# Sheet2_0.net
KiCad netlist of a schematic drawn in Altium Designer
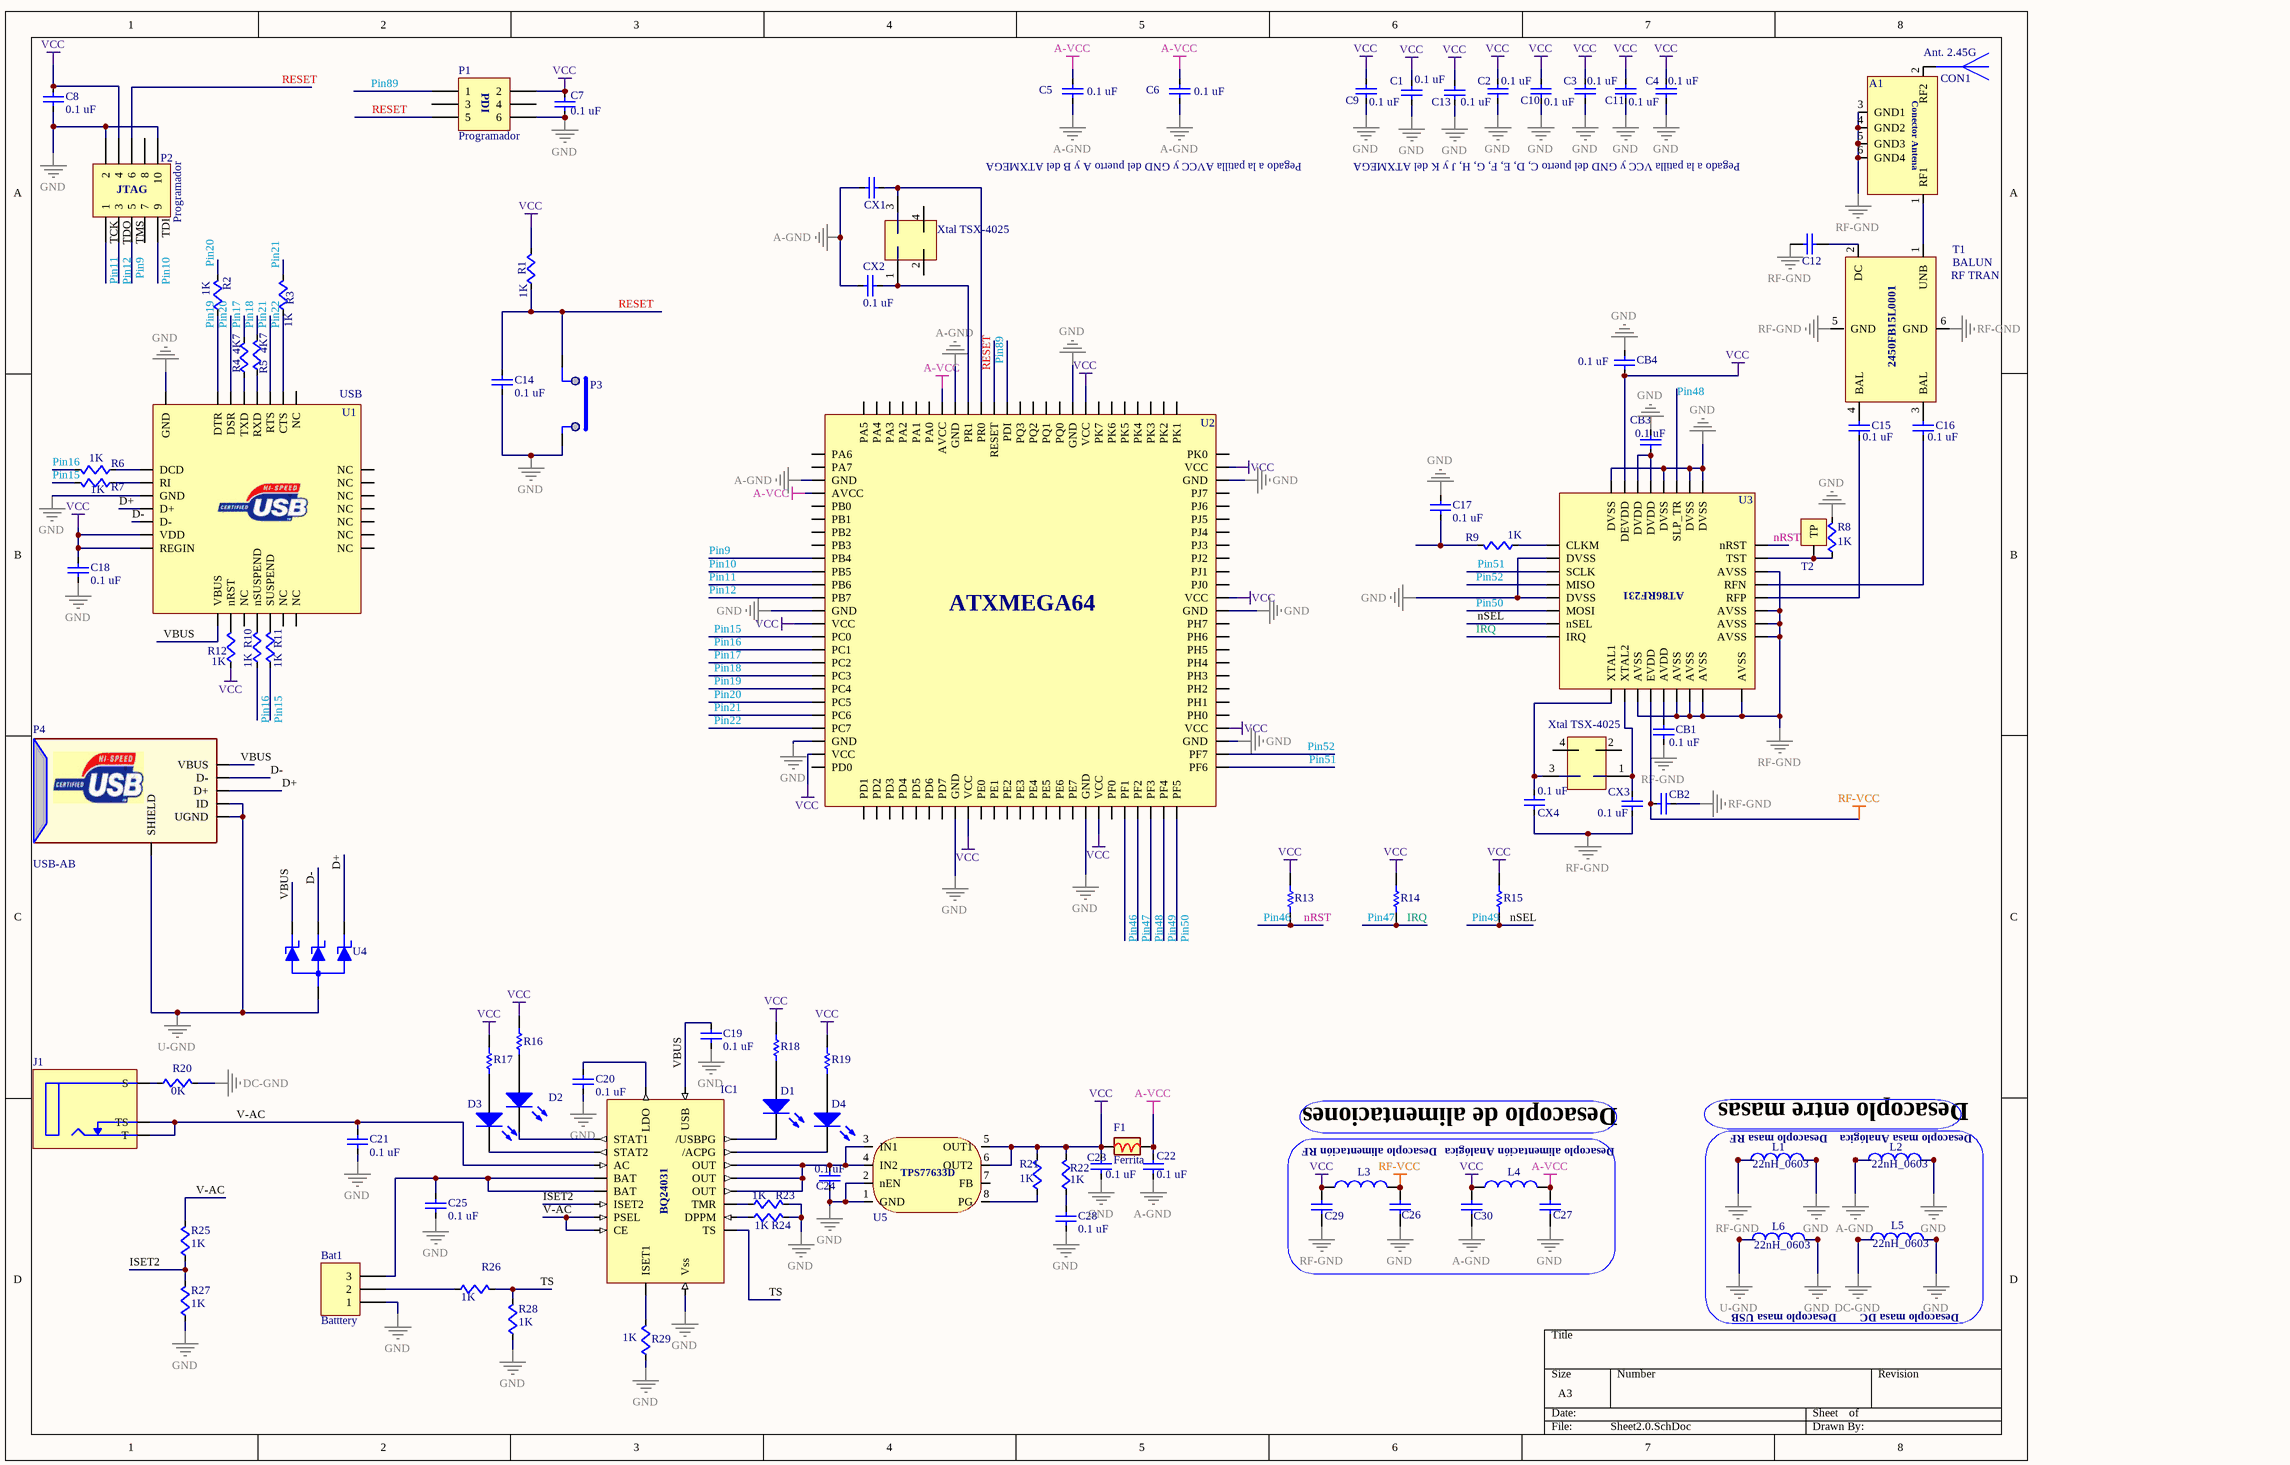
[diagram p0: Sheet2.0.SchDoc]

(export (version "E")
  (design (tool "Eeschema 10.0.6"))
  (components
    (comp (ref "A1")
      (value "Ant. 2.45G")
      (footprint "ANTENNA CHIP")
      (description "ANTENNA CHIP 2.4GHZ")
      (libsource (lib "Mia") (part "2450AT18A100"))
    )
    (comp (ref "Bat1")
      (value "Batttery")
      (footprint "HDR1X3")
      (description "Header, 3-Pin")
      (fields (field (name "PUBLISHER") "Altium Limited"))
      (libsource (lib "Mia") (part "Header 3"))
    )
    (comp (ref "C1")
      (value "C")
      (footprint "0402")
      (description "CONDENSADOR")
      (fields (field (name "VALOR") "0.1 uF"))
      (libsource (lib "Mia") (part "C"))
    )
    (comp (ref "C2")
      (value "C")
      (footprint "0402")
      (description "CONDENSADOR")
      (fields (field (name "VALOR") "0.1 uF"))
      (libsource (lib "Mia") (part "C"))
    )
    (comp (ref "C3")
      (value "C")
      (footprint "0402")
      (description "CONDENSADOR")
      (fields (field (name "VALOR") "0.1 uF"))
      (libsource (lib "Mia") (part "C"))
    )
    (comp (ref "C4")
      (value "C")
      (footprint "0402")
      (description "CONDENSADOR")
      (fields (field (name "VALOR") "0.1 uF"))
      (libsource (lib "Mia") (part "C"))
    )
    (comp (ref "C5")
      (value "C")
      (footprint "0402")
      (description "CONDENSADOR")
      (fields (field (name "VALOR") "0.1 uF"))
      (libsource (lib "Mia") (part "C"))
    )
    (comp (ref "C6")
      (value "C")
      (footprint "0402")
      (description "CONDENSADOR")
      (fields (field (name "VALOR") "0.1 uF"))
      (libsource (lib "Mia") (part "C"))
    )
    (comp (ref "C7")
      (value "C")
      (footprint "0402")
      (description "CONDENSADOR")
      (fields (field (name "VALOR") "0.1 uF"))
      (libsource (lib "Mia") (part "C"))
    )
    (comp (ref "C8")
      (value "C")
      (footprint "0402")
      (description "CONDENSADOR")
      (fields (field (name "VALOR") "0.1 uF"))
      (libsource (lib "Mia") (part "C"))
    )
    (comp (ref "C9")
      (value "C")
      (footprint "0402")
      (description "CONDENSADOR")
      (fields (field (name "VALOR") "0.1 uF"))
      (libsource (lib "Mia") (part "C"))
    )
    (comp (ref "C10")
      (value "C")
      (footprint "0402")
      (description "CONDENSADOR")
      (fields (field (name "VALOR") "0.1 uF"))
      (libsource (lib "Mia") (part "C"))
    )
    (comp (ref "C11")
      (value "C")
      (footprint "0402")
      (description "CONDENSADOR")
      (fields (field (name "VALOR") "0.1 uF"))
      (libsource (lib "Mia") (part "C"))
    )
    (comp (ref "C12")
      (value "22pF_0402")
      (footprint "0402")
      (description "CAP CER 56PF 50V 5% C0G 0402")
      (libsource (lib "Mia") (part "56pF_0402"))
    )
    (comp (ref "C13")
      (value "C")
      (footprint "0402")
      (description "CONDENSADOR")
      (fields (field (name "VALOR") "0.1 uF"))
      (libsource (lib "Mia") (part "C"))
    )
    (comp (ref "C14")
      (value "C")
      (footprint "0402")
      (description "CONDENSADOR")
      (fields (field (name "VALOR") "0.1 uF"))
      (libsource (lib "Mia") (part "C"))
    )
    (comp (ref "C15")
      (value "C")
      (footprint "0402")
      (description "CONDENSADOR")
      (fields (field (name "VALOR") "0.1 uF"))
      (libsource (lib "Mia") (part "C"))
    )
    (comp (ref "C16")
      (value "C")
      (footprint "0402")
      (description "CONDENSADOR")
      (fields (field (name "VALOR") "0.1 uF"))
      (libsource (lib "Mia") (part "C"))
    )
    (comp (ref "C17")
      (value "C")
      (footprint "0402")
      (description "CONDENSADOR")
      (fields (field (name "VALOR") "0.1 uF"))
      (libsource (lib "Mia") (part "C"))
    )
    (comp (ref "C18")
      (value "C")
      (footprint "0402")
      (description "CONDENSADOR")
      (fields (field (name "VALOR") "0.1 uF"))
      (libsource (lib "Mia") (part "C"))
    )
    (comp (ref "C19")
      (value "C")
      (footprint "0402")
      (description "CONDENSADOR")
      (fields (field (name "VALOR") "0.1 uF"))
      (libsource (lib "Mia") (part "C"))
    )
    (comp (ref "C20")
      (value "C")
      (footprint "0402")
      (description "CONDENSADOR")
      (fields (field (name "VALOR") "0.1 uF"))
      (libsource (lib "Mia") (part "C"))
    )
    (comp (ref "C21")
      (value "C")
      (footprint "0402")
      (description "CONDENSADOR")
      (fields (field (name "VALOR") "0.1 uF"))
      (libsource (lib "Mia") (part "C"))
    )
    (comp (ref "C22")
      (value "C")
      (footprint "0402")
      (description "CONDENSADOR")
      (fields (field (name "VALOR") "0.1 uF"))
      (libsource (lib "Mia") (part "C"))
    )
    (comp (ref "C23")
      (value "C")
      (footprint "0402")
      (description "CONDENSADOR")
      (fields (field (name "VALOR") "0.1 uF"))
      (libsource (lib "Mia") (part "C"))
    )
    (comp (ref "C24")
      (value "C")
      (footprint "0402")
      (description "CONDENSADOR")
      (fields (field (name "VALOR") "0.1 uF"))
      (libsource (lib "Mia") (part "C"))
    )
    (comp (ref "C25")
      (value "C")
      (footprint "0402")
      (description "CONDENSADOR")
      (fields (field (name "VALOR") "0.1 uF"))
      (libsource (lib "Mia") (part "C"))
    )
    (comp (ref "C26")
      (value "100nF_0805")
      (footprint "0805")
      (description "CAP CER 100PF 630V X7R 0805")
      (libsource (lib "Mia") (part "100nF_0805"))
    )
    (comp (ref "C27")
      (value "100nF_0805")
      (footprint "0805")
      (description "CAP CER 100PF 630V X7R 0805")
      (libsource (lib "Mia") (part "100nF_0805"))
    )
    (comp (ref "C28")
      (value "C")
      (footprint "0402")
      (description "CONDENSADOR")
      (fields (field (name "VALOR") "0.1 uF"))
      (libsource (lib "Mia") (part "C"))
    )
    (comp (ref "C29")
      (value "100nF_0805")
      (footprint "0805")
      (description "CAP CER 100PF 630V X7R 0805")
      (libsource (lib "Mia") (part "100nF_0805"))
    )
    (comp (ref "C30")
      (value "100nF_0805")
      (footprint "0805")
      (description "CAP CER 100PF 630V X7R 0805")
      (libsource (lib "Mia") (part "100nF_0805"))
    )
    (comp (ref "CB1")
      (value "C")
      (footprint "0402")
      (description "CONDENSADOR")
      (fields (field (name "VALOR") "0.1 uF"))
      (libsource (lib "Mia") (part "C"))
    )
    (comp (ref "CB2")
      (value "C")
      (footprint "0402")
      (description "CONDENSADOR")
      (fields (field (name "VALOR") "0.1 uF"))
      (libsource (lib "Mia") (part "C"))
    )
    (comp (ref "CB3")
      (value "C")
      (footprint "0402")
      (description "CONDENSADOR")
      (fields (field (name "VALOR") "0.1 uF"))
      (libsource (lib "Mia") (part "C"))
    )
    (comp (ref "CB4")
      (value "C")
      (footprint "0402")
      (description "CONDENSADOR")
      (fields (field (name "VALOR") "0.1 uF"))
      (libsource (lib "Mia") (part "C"))
    )
    (comp (ref "CON1")
      (value "Conector Antena")
      (footprint "MM8430-2600_Coaxial Connectors")
      (description "CONN MW COAXIAL WITH SWITCH")
      (libsource (lib "Mia") (part "CON ANT-MM8430-2600RA1"))
    )
    (comp (ref "CX1")
      (value "C")
      (footprint "0402")
      (description "CONDENSADOR")
      (libsource (lib "Mia") (part "C"))
    )
    (comp (ref "CX2")
      (value "C")
      (footprint "0402")
      (description "CONDENSADOR")
      (fields (field (name "VALOR") "0.1 uF"))
      (libsource (lib "Mia") (part "C"))
    )
    (comp (ref "CX3")
      (value "C")
      (footprint "0402")
      (description "CONDENSADOR")
      (fields (field (name "VALOR") "0.1 uF"))
      (libsource (lib "Mia") (part "C"))
    )
    (comp (ref "CX4")
      (value "C")
      (footprint "0402")
      (description "CONDENSADOR")
      (libsource (lib "Mia") (part "C"))
    )
    (comp (ref "D1")
      (value "Diodo Led")
      (footprint "Diode Led")
      (description "Typical INFRARED GaAs LED")
      (libsource (lib "Mia") (part "LTST-C230CKT"))
    )
    (comp (ref "D2")
      (value "Diodo Led")
      (footprint "Diode Led")
      (description "Typical INFRARED GaAs LED")
      (libsource (lib "Mia") (part "LTST-C230CKT"))
    )
    (comp (ref "D3")
      (value "Diodo Led")
      (footprint "Diode Led")
      (description "Typical INFRARED GaAs LED")
      (libsource (lib "Mia") (part "LTST-C230CKT"))
    )
    (comp (ref "D4")
      (value "Diodo Led")
      (footprint "Diode Led")
      (description "Typical INFRARED GaAs LED")
      (libsource (lib "Mia") (part "LTST-C230CKT"))
    )
    (comp (ref "F1")
      (value "Ferrita")
      (footprint "0603")
      (description "Chip Ferrite Beads")
      (libsource (lib "Mia") (part "BLM21AH102SN1"))
    )
    (comp (ref "IC1")
      (value "BQ24031")
      (footprint "BQ24031")
      (description "IC PWR MANAGEMENT SYSTEM 20-QFN")
      (libsource (lib "Mia") (part "BQ24031"))
    )
    (comp (ref "J1")
      (value "CAMSHOT")
      (footprint "MJ-2509N")
      (description "CONN MONO JACK 2.5MM PCB MNT")
      (libsource (lib "*") (part "MJ-2509N_1"))
    )
    (comp (ref "L1")
      (value "22nH_0603")
      (footprint "0603")
      (description "CER INDUCTOR 22NH 0603")
      (libsource (lib "Mia") (part "22nH_0603"))
    )
    (comp (ref "L2")
      (value "22nH_0603")
      (footprint "0603")
      (description "CER INDUCTOR 22NH 0603")
      (libsource (lib "Mia") (part "22nH_0603"))
    )
    (comp (ref "L3")
      (value "22nH_0603")
      (footprint "0603")
      (description "CER INDUCTOR 22NH 0603")
      (libsource (lib "Mia") (part "22nH_0603"))
    )
    (comp (ref "L4")
      (value "22nH_0603")
      (footprint "0603")
      (description "CER INDUCTOR 22NH 0603")
      (libsource (lib "Mia") (part "22nH_0603"))
    )
    (comp (ref "L5")
      (value "22nH_0603")
      (footprint "0603")
      (description "CER INDUCTOR 22NH 0603")
      (libsource (lib "Mia") (part "22nH_0603"))
    )
    (comp (ref "L6")
      (value "22nH_0603")
      (footprint "0603")
      (description "CER INDUCTOR 22NH 0603")
      (libsource (lib "Mia") (part "22nH_0603"))
    )
    (comp (ref "P1")
      (value "Programador")
      (footprint "HDR2X3")
      (description "Header, 3-Pin, Dual row")
      (fields (field (name "PUBLISHER") "Altium Limited"))
      (libsource (lib "Mia") (part "Header 3X2"))
    )
    (comp (ref "P2")
      (value "Programador")
      (footprint "HDR2X5")
      (description "Header, 5-Pin, Dual row")
      (fields (field (name "PUBLISHER") "Altium Limited"))
      (libsource (lib "Mia") (part "Header 5X2"))
    )
    (comp (ref "P3")
      (value "Pulsador")
      (footprint "PUSH-BUTTON-W")
      (description "SWITCH TACT 6X3.5MM H=4.3MM 180G")
      (libsource (lib "Mia") (part "PUSHBUTTON"))
    )
    (comp (ref "P4")
      (value "USB-AB")
      (footprint "USB-MINI-AB-SMT")
      (description "CONN RECEPT USB 5POS RT ANG SMD")
      (libsource (lib "Mia") (part "WM1722"))
    )
    (comp (ref "R1")
      (value "1K")
      (footprint "0603")
      (description "RESISTENCIA 0402 SMD")
      (fields (field (name "Comment") "R 0402"))
      (libsource (lib "Mia") (part "R 0402"))
    )
    (comp (ref "R2")
      (value "1K")
      (footprint "0603")
      (description "RESISTENCIA 0402 SMD")
      (fields (field (name "Comment") "R 0402"))
      (libsource (lib "Mia") (part "R 0402"))
    )
    (comp (ref "R3")
      (value "1K")
      (footprint "0603")
      (description "RESISTENCIA 0402 SMD")
      (fields (field (name "Comment") "R 0402"))
      (libsource (lib "Mia") (part "R 0402"))
    )
    (comp (ref "R4")
      (value "4K7")
      (footprint "0603")
      (description "RESISTENCIA 0402 SMD")
      (fields (field (name "Comment") "R 0402"))
      (libsource (lib "Mia") (part "R 0402"))
    )
    (comp (ref "R5")
      (value "4K7")
      (footprint "0603")
      (description "RESISTENCIA 0402 SMD")
      (fields (field (name "Comment") "R 0402"))
      (libsource (lib "Mia") (part "R 0402"))
    )
    (comp (ref "R6")
      (value "1K")
      (footprint "0603")
      (description "RESISTENCIA 0402 SMD")
      (fields (field (name "Comment") "R 0402"))
      (libsource (lib "Mia") (part "R 0402"))
    )
    (comp (ref "R7")
      (value "1K")
      (footprint "0603")
      (description "RESISTENCIA 0402 SMD")
      (fields (field (name "Comment") "R 0402"))
      (libsource (lib "Mia") (part "R 0402"))
    )
    (comp (ref "R8")
      (value "1K")
      (footprint "0603")
      (description "RESISTENCIA 0402 SMD")
      (fields (field (name "Comment") "R 0402"))
      (libsource (lib "Mia") (part "R 0402"))
    )
    (comp (ref "R9")
      (value "1K")
      (footprint "0603")
      (description "RESISTENCIA 0402 SMD")
      (fields (field (name "Comment") "R 0402"))
      (libsource (lib "Mia") (part "R 0402"))
    )
    (comp (ref "R10")
      (value "1K")
      (footprint "0603")
      (description "RESISTENCIA 0402 SMD")
      (fields (field (name "Comment") "R 0402"))
      (libsource (lib "Mia") (part "R 0402"))
    )
    (comp (ref "R11")
      (value "1K")
      (footprint "0603")
      (description "RESISTENCIA 0402 SMD")
      (fields (field (name "Comment") "R 0402"))
      (libsource (lib "Mia") (part "R 0402"))
    )
    (comp (ref "R12")
      (value "1K")
      (footprint "0603")
      (description "RESISTENCIA 0402 SMD")
      (fields (field (name "Comment") "R 0402"))
      (libsource (lib "Mia") (part "R 0402"))
    )
    (comp (ref "R13")
      (value "16.9kohm-0805")
      (footprint "0805")
      (description "RES 16.9K OHM 1/8W 1% 0805 SMD")
      (libsource (lib "Mia") (part "16.9kohm-0805"))
    )
    (comp (ref "R14")
      (value "16.9kohm-0805")
      (footprint "0805")
      (description "RES 16.9K OHM 1/8W 1% 0805 SMD")
      (libsource (lib "Mia") (part "16.9kohm-0805"))
    )
    (comp (ref "R15")
      (value "16.9kohm-0805")
      (footprint "0805")
      (description "RES 16.9K OHM 1/8W 1% 0805 SMD")
      (libsource (lib "Mia") (part "16.9kohm-0805"))
    )
    (comp (ref "R16")
      (value "16.9kohm-0805")
      (footprint "0805")
      (description "RES 16.9K OHM 1/8W 1% 0805 SMD")
      (libsource (lib "Mia") (part "16.9kohm-0805"))
    )
    (comp (ref "R17")
      (value "16.9kohm-0805")
      (footprint "0805")
      (description "RES 16.9K OHM 1/8W 1% 0805 SMD")
      (libsource (lib "Mia") (part "16.9kohm-0805"))
    )
    (comp (ref "R18")
      (value "16.9kohm-0805")
      (footprint "0805")
      (description "RES 16.9K OHM 1/8W 1% 0805 SMD")
      (libsource (lib "Mia") (part "16.9kohm-0805"))
    )
    (comp (ref "R19")
      (value "16.9kohm-0805")
      (footprint "0805")
      (description "RES 16.9K OHM 1/8W 1% 0805 SMD")
      (libsource (lib "Mia") (part "16.9kohm-0805"))
    )
    (comp (ref "R20")
      (value "0K")
      (footprint "0603")
      (description "RESISTENCIA 0402 SMD")
      (fields (field (name "Comment") "R 0402"))
      (libsource (lib "Mia") (part "R 0402"))
    )
    (comp (ref "R21")
      (value "1K")
      (footprint "0603")
      (description "RESISTENCIA 0402 SMD")
      (fields (field (name "Comment") "R 0402"))
      (libsource (lib "Mia") (part "R 0402"))
    )
    (comp (ref "R22")
      (value "1K")
      (footprint "0603")
      (description "RESISTENCIA 0402 SMD")
      (fields (field (name "Comment") "R 0402"))
      (libsource (lib "Mia") (part "R 0402"))
    )
    (comp (ref "R23")
      (value "1K")
      (footprint "0603")
      (description "RESISTENCIA 0402 SMD")
      (fields (field (name "Comment") "R 0402"))
      (libsource (lib "Mia") (part "R 0402"))
    )
    (comp (ref "R24")
      (value "1K")
      (footprint "0603")
      (description "RESISTENCIA 0402 SMD")
      (fields (field (name "Comment") "R 0402"))
      (libsource (lib "Mia") (part "R 0402"))
    )
    (comp (ref "R25")
      (value "1K")
      (footprint "0603")
      (description "RESISTENCIA 0402 SMD")
      (fields (field (name "Comment") "R 0402"))
      (libsource (lib "Mia") (part "R 0402"))
    )
    (comp (ref "R26")
      (value "1K")
      (footprint "0603")
      (description "RESISTENCIA 0402 SMD")
      (fields (field (name "Comment") "R 0402"))
      (libsource (lib "Mia") (part "R 0402"))
    )
    (comp (ref "R27")
      (value "1K")
      (footprint "0603")
      (description "RESISTENCIA 0402 SMD")
      (fields (field (name "Comment") "R 0402"))
      (libsource (lib "Mia") (part "R 0402"))
    )
    (comp (ref "R28")
      (value "1K")
      (footprint "0603")
      (description "RESISTENCIA 0402 SMD")
      (fields (field (name "Comment") "R 0402"))
      (libsource (lib "Mia") (part "R 0402"))
    )
    (comp (ref "R29")
      (value "1K")
      (footprint "0603")
      (description "RESISTENCIA 0402 SMD")
      (fields (field (name "Comment") "R 0402"))
      (libsource (lib "Mia") (part "R 0402"))
    )
    (comp (ref "T1")
      (value "BALUN")
      (footprint "BALUN")
      (description "FILTER BALUN CER CHIP 2.4GHZ")
      (libsource (lib "Mia") (part "2450FB39B100E"))
    )
    (comp (ref "T2")
      (value "TESTPOINT")
      (footprint "TESTPOINT")
      (description "Punto de Test")
      (libsource (lib "Mia") (part "TESTPOINT"))
    )
    (comp (ref "U1")
      (value "USB")
      (footprint "QFN28_5X5")
      (description "IC USB-TO-UART BRIDGE 28MLP")
      (libsource (lib "Mia") (part "CP2102"))
    )
    (comp (ref "U2")
      (value "XMEGA")
      (footprint "Quad100")
      (description "MCU AVR 64K FLASH 1.6V 100-TQFP")
      (libsource (lib "Mia") (part "ATXMEGA64A1"))
    )
    (comp (ref "U3")
      (value "RF TRAN")
      (footprint "QFN32_50")
      (description "IC TXRX ZIGBEE/802.15.4 32QFN")
      (libsource (lib "Mia") (part "AT86RF231"))
    )
    (comp (ref "U4")
      (value "TVS")
      (footprint "SOT-143")
      (description "TVS AVAL DIODE ARRAY 3 CH SOT143")
      (libsource (lib "Mia") (part "SP0503BAHTG"))
    )
    (comp (ref "U5")
      (value "TPS77633D")
      (footprint "TPS77633D")
      (description "IC 3.3V 500MA LDO REG 8-SOIC")
      (libsource (lib "Mia") (part "TPS77633D"))
    )
    (comp (ref "Xtal1")
      (value "Xtal TSX-4025")
      (footprint "TSX-4025")
      (description "Cristal 16Mhz")
      (libsource (lib "Mia") (part "Xtal TSX-4025"))
    )
    (comp (ref "Xtal2")
      (value "Xtal TSX-4025")
      (footprint "TSX-4025")
      (description "Cristal 16Mhz")
      (libsource (lib "") (part "Xtal TSX-4025_1"))
    )
  )
  (nets
    (net (code "1") (name "/D+") (class "Default")
      (node (ref "P4") (pin "D+") (pinfunction "D+_D+") (pintype "passive"))
      (node (ref "U1") (pin "4") (pinfunction "D+_4") (pintype "passive"))
      (node (ref "U4") (pin "2") (pinfunction "C_2") (pintype "passive"))
    )
    (net (code "2") (name "/D-") (class "Default")
      (node (ref "P4") (pin "D-") (pinfunction "D-_D-") (pintype "passive"))
      (node (ref "U1") (pin "5") (pinfunction "D-_5") (pintype "passive"))
      (node (ref "U4") (pin "3") (pinfunction "C_3") (pintype "passive"))
    )
    (net (code "3") (name "/IRQ") (class "Default")
      (node (ref "R14") (pin "1") (pinfunction "1_1") (pintype "passive"))
      (node (ref "U2") (pin "47") (pinfunction "PF2_47") (pintype "passive"))
      (node (ref "U3") (pin "24") (pinfunction "IRQ_24") (pintype "passive"))
    )
    (net (code "4") (name "/ISET2") (class "Default")
      (node (ref "IC1") (pin "7") (pinfunction "ISET2_7") (pintype "input"))
      (node (ref "R25") (pin "1") (pinfunction "1_1") (pintype "passive"))
      (node (ref "R27") (pin "2") (pinfunction "2_2") (pintype "passive"))
    )
    (net (code "5") (name "/Pin9") (class "Default")
      (node (ref "P2") (pin "5") (pinfunction "5_5") (pintype "passive"))
      (node (ref "U2") (pin "9") (pinfunction "PB4_9") (pintype "passive"))
    )
    (net (code "6") (name "/Pin10") (class "Default")
      (node (ref "P2") (pin "9") (pinfunction "9_9") (pintype "passive"))
      (node (ref "U2") (pin "10") (pinfunction "PB5_10") (pintype "passive"))
    )
    (net (code "7") (name "/Pin11") (class "Default")
      (node (ref "P2") (pin "1") (pinfunction "1_1") (pintype "passive"))
      (node (ref "U2") (pin "11") (pinfunction "PB6_11") (pintype "passive"))
    )
    (net (code "8") (name "/Pin12") (class "Default")
      (node (ref "P2") (pin "3") (pinfunction "3_3") (pintype "passive"))
      (node (ref "U2") (pin "12") (pinfunction "PB7_12") (pintype "passive"))
    )
    (net (code "9") (name "/Pin15") (class "Default")
      (node (ref "R11") (pin "1") (pinfunction "1_1") (pintype "passive"))
      (node (ref "R7") (pin "2") (pinfunction "2_2") (pintype "passive"))
      (node (ref "U2") (pin "15") (pinfunction "PC0_15") (pintype "passive"))
    )
    (net (code "10") (name "/Pin16") (class "Default")
      (node (ref "R10") (pin "1") (pinfunction "1_1") (pintype "passive"))
      (node (ref "R6") (pin "2") (pinfunction "2_2") (pintype "passive"))
      (node (ref "U2") (pin "16") (pinfunction "PC1_16") (pintype "passive"))
    )
    (net (code "11") (name "/Pin17") (class "Default")
      (node (ref "R4") (pin "2") (pinfunction "2_2") (pintype "passive"))
      (node (ref "U2") (pin "17") (pinfunction "PC2_17") (pintype "passive"))
    )
    (net (code "12") (name "/Pin18") (class "Default")
      (node (ref "R5") (pin "2") (pinfunction "2_2") (pintype "passive"))
      (node (ref "U2") (pin "18") (pinfunction "PC3_18") (pintype "passive"))
    )
    (net (code "13") (name "/Pin19") (class "Default")
      (node (ref "R2") (pin "1") (pinfunction "1_1") (pintype "passive"))
      (node (ref "U1") (pin "28") (pinfunction "DTR_28") (pintype "passive"))
      (node (ref "U2") (pin "19") (pinfunction "PC4_19") (pintype "passive"))
    )
    (net (code "14") (name "/Pin20") (class "Default")
      (node (ref "R2") (pin "2") (pinfunction "2_2") (pintype "passive"))
      (node (ref "U1") (pin "27") (pinfunction "DSR_27") (pintype "passive"))
      (node (ref "U2") (pin "20") (pinfunction "PC5_20") (pintype "passive"))
    )
    (net (code "15") (name "/Pin21") (class "Default")
      (node (ref "R3") (pin "2") (pinfunction "2_2") (pintype "passive"))
      (node (ref "U1") (pin "24") (pinfunction "RTS_24") (pintype "passive"))
      (node (ref "U2") (pin "21") (pinfunction "PC6_21") (pintype "passive"))
    )
    (net (code "16") (name "/Pin22") (class "Default")
      (node (ref "R3") (pin "1") (pinfunction "1_1") (pintype "passive"))
      (node (ref "U1") (pin "23") (pinfunction "CTS_23") (pintype "passive"))
      (node (ref "U2") (pin "22") (pinfunction "PC7_22") (pintype "passive"))
    )
    (net (code "17") (name "/Pin46") (class "Default")
      (node (ref "R13") (pin "1") (pinfunction "1_1") (pintype "passive"))
      (node (ref "U2") (pin "46") (pinfunction "PF1_46") (pintype "passive"))
      (node (ref "U3") (pin "8") (pinfunction "nRST_8") (pintype "passive"))
    )
    (net (code "18") (name "/Pin48") (class "Default")
      (node (ref "U2") (pin "48") (pinfunction "PF3_48") (pintype "passive"))
      (node (ref "U3") (pin "11") (pinfunction "SLP_TR_11") (pintype "passive"))
    )
    (net (code "19") (name "/Pin49") (class "Default")
      (node (ref "R15") (pin "1") (pinfunction "1_1") (pintype "passive"))
      (node (ref "U2") (pin "49") (pinfunction "PF4_49") (pintype "passive"))
      (node (ref "U3") (pin "23") (pinfunction "nSEL_23") (pintype "passive"))
    )
    (net (code "20") (name "/Pin50") (class "Default")
      (node (ref "U2") (pin "50") (pinfunction "PF5_50") (pintype "passive"))
      (node (ref "U3") (pin "22") (pinfunction "MOSI_22") (pintype "passive"))
    )
    (net (code "21") (name "/Pin51") (class "Default")
      (node (ref "U2") (pin "51") (pinfunction "PF6_51") (pintype "passive"))
      (node (ref "U3") (pin "19") (pinfunction "SCLK_19") (pintype "passive"))
    )
    (net (code "22") (name "/Pin52") (class "Default")
      (node (ref "U2") (pin "52") (pinfunction "PF7_52") (pintype "passive"))
      (node (ref "U3") (pin "20") (pinfunction "MISO_20") (pintype "passive"))
    )
    (net (code "23") (name "/Pin89") (class "Default")
      (node (ref "P1") (pin "1") (pinfunction "1_1") (pintype "passive"))
      (node (ref "U2") (pin "89") (pinfunction "PDI_89") (pintype "passive"))
    )
    (net (code "24") (name "/RESET") (class "Default")
      (node (ref "C14") (pin "1") (pinfunction "1_1") (pintype "passive"))
      (node (ref "P1") (pin "5") (pinfunction "5_5") (pintype "passive"))
      (node (ref "P2") (pin "6") (pinfunction "6_6") (pintype "passive"))
      (node (ref "P3") (pin "1") (pinfunction "1_1") (pintype "passive"))
      (node (ref "R1") (pin "1") (pinfunction "1_1") (pintype "passive"))
      (node (ref "U2") (pin "90") (pinfunction "RESET_90") (pintype "passive"))
    )
    (net (code "29") (name "/TS") (class "Default")
      (node (ref "IC1") (pin "12") (pinfunction "TS_12") (pintype "bidirectional"))
      (node (ref "R26") (pin "2") (pinfunction "2_2") (pintype "passive"))
      (node (ref "R28") (pin "2") (pinfunction "2_2") (pintype "passive"))
    )
    (net (code "30") (name "/V-AC") (class "Default")
      (node (ref "C21") (pin "1") (pinfunction "1_1") (pintype "passive"))
      (node (ref "IC1") (pin "4") (pinfunction "AC_4") (pintype "input"))
      (node (ref "IC1") (pin "8") (pinfunction "PSEL_8") (pintype "input"))
      (node (ref "IC1") (pin "9") (pinfunction "CE_9") (pintype "input"))
      (node (ref "J1") (pin "2") (pinfunction "T_2") (pintype "passive"))
      (node (ref "J1") (pin "3") (pinfunction "TS_3") (pintype "passive"))
      (node (ref "R25") (pin "2") (pinfunction "2_2") (pintype "passive"))
    )
    (net (code "31") (name "/VBUS") (class "Default")
      (node (ref "C19") (pin "1") (pinfunction "1_1") (pintype "passive"))
      (node (ref "IC1") (pin "20") (pinfunction "USB_20") (pintype "input"))
      (node (ref "P4") (pin "VBUS") (pinfunction "VBUS_VBUS") (pintype "passive"))
      (node (ref "U1") (pin "8") (pinfunction "VBUS_8") (pintype "passive"))
      (node (ref "U4") (pin "4") (pinfunction "C_4") (pintype "passive"))
    )
    (net (code "32") (name "A-GND") (class "Default")
      (node (ref "C22") (pin "2") (pinfunction "2_2") (pintype "passive"))
      (node (ref "C30") (pin "1") (pinfunction "1_1") (pintype "passive"))
      (node (ref "C5") (pin "2") (pinfunction "2_2") (pintype "passive"))
      (node (ref "C6") (pin "2") (pinfunction "2_2") (pintype "passive"))
      (node (ref "CX1") (pin "1") (pinfunction "1_1") (pintype "passive"))
      (node (ref "CX2") (pin "1") (pinfunction "1_1") (pintype "passive"))
      (node (ref "L2") (pin "1") (pinfunction "1_1") (pintype "passive"))
      (node (ref "U2") (pin "3") (pinfunction "GND_3") (pintype "passive"))
      (node (ref "U2") (pin "93") (pinfunction "GND_93") (pintype "passive"))
    )
    (net (code "33") (name "A-VCC") (class "Default")
      (node (ref "C22") (pin "1") (pinfunction "1_1") (pintype "passive"))
      (node (ref "C27") (pin "2") (pinfunction "2_2") (pintype "passive"))
      (node (ref "C5") (pin "1") (pinfunction "1_1") (pintype "passive"))
      (node (ref "C6") (pin "1") (pinfunction "1_1") (pintype "passive"))
      (node (ref "F1") (pin "2") (pinfunction "Y_2") (pintype "passive"))
      (node (ref "L4") (pin "2") (pinfunction "2_2") (pintype "passive"))
      (node (ref "U2") (pin "4") (pinfunction "AVCC_4") (pintype "passive"))
      (node (ref "U2") (pin "94") (pinfunction "AVCC_94") (pintype "passive"))
    )
    (net (code "34") (name "DC-GND") (class "Default")
      (node (ref "L5") (pin "1") (pinfunction "1_1") (pintype "passive"))
      (node (ref "R20") (pin "2") (pinfunction "2_2") (pintype "passive"))
    )
    (net (code "35") (name "GND") (class "Default")
      (node (ref "Bat1") (pin "1") (pinfunction "1_1") (pintype "passive"))
      (node (ref "C1") (pin "2") (pinfunction "2_2") (pintype "passive"))
      (node (ref "C10") (pin "2") (pinfunction "2_2") (pintype "passive"))
      (node (ref "C11") (pin "2") (pinfunction "2_2") (pintype "passive"))
      (node (ref "C13") (pin "2") (pinfunction "2_2") (pintype "passive"))
      (node (ref "C14") (pin "2") (pinfunction "2_2") (pintype "passive"))
      (node (ref "C17") (pin "1") (pinfunction "1_1") (pintype "passive"))
      (node (ref "C18") (pin "2") (pinfunction "2_2") (pintype "passive"))
      (node (ref "C19") (pin "2") (pinfunction "2_2") (pintype "passive"))
      (node (ref "C2") (pin "2") (pinfunction "2_2") (pintype "passive"))
      (node (ref "C20") (pin "2") (pinfunction "2_2") (pintype "passive"))
      (node (ref "C21") (pin "2") (pinfunction "2_2") (pintype "passive"))
      (node (ref "C23") (pin "2") (pinfunction "2_2") (pintype "passive"))
      (node (ref "C24") (pin "2") (pinfunction "2_2") (pintype "passive"))
      (node (ref "C25") (pin "2") (pinfunction "2_2") (pintype "passive"))
      (node (ref "C26") (pin "1") (pinfunction "1_1") (pintype "passive"))
      (node (ref "C27") (pin "1") (pinfunction "1_1") (pintype "passive"))
      (node (ref "C28") (pin "2") (pinfunction "2_2") (pintype "passive"))
      (node (ref "C3") (pin "2") (pinfunction "2_2") (pintype "passive"))
      (node (ref "C4") (pin "2") (pinfunction "2_2") (pintype "passive"))
      (node (ref "C7") (pin "2") (pinfunction "2_2") (pintype "passive"))
      (node (ref "C8") (pin "2") (pinfunction "2_2") (pintype "passive"))
      (node (ref "C9") (pin "2") (pinfunction "2_2") (pintype "passive"))
      (node (ref "CB3") (pin "1") (pinfunction "1_1") (pintype "passive"))
      (node (ref "CB4") (pin "2") (pinfunction "2_2") (pintype "passive"))
      (node (ref "IC1") (pin "11") (pinfunction "Vss_11") (pintype "input"))
      (node (ref "L1") (pin "2") (pinfunction "2_2") (pintype "passive"))
      (node (ref "L2") (pin "2") (pinfunction "2_2") (pintype "passive"))
      (node (ref "L5") (pin "2") (pinfunction "2_2") (pintype "passive"))
      (node (ref "L6") (pin "2") (pinfunction "2_2") (pintype "passive"))
      (node (ref "P1") (pin "6") (pinfunction "6_6") (pintype "passive"))
      (node (ref "P2") (pin "10") (pinfunction "10_10") (pintype "passive"))
      (node (ref "P2") (pin "2") (pinfunction "2_2") (pintype "passive"))
      (node (ref "P3") (pin "2") (pinfunction "2_2") (pintype "passive"))
      (node (ref "R23") (pin "2") (pinfunction "2_2") (pintype "passive"))
      (node (ref "R24") (pin "2") (pinfunction "2_2") (pintype "passive"))
      (node (ref "R27") (pin "1") (pinfunction "1_1") (pintype "passive"))
      (node (ref "R28") (pin "1") (pinfunction "1_1") (pintype "passive"))
      (node (ref "R29") (pin "1") (pinfunction "1_1") (pintype "passive"))
      (node (ref "R8") (pin "2") (pinfunction "2_2") (pintype "passive"))
      (node (ref "U1") (pin "0") (pinfunction "GND_0") (pintype "passive"))
      (node (ref "U1") (pin "3") (pinfunction "GND_3") (pintype "passive"))
      (node (ref "U2") (pin "13") (pinfunction "GND_13") (pintype "passive"))
      (node (ref "U2") (pin "23") (pinfunction "GND_23") (pintype "passive"))
      (node (ref "U2") (pin "33") (pinfunction "GND_33") (pintype "passive"))
      (node (ref "U2") (pin "43") (pinfunction "GND_43") (pintype "passive"))
      (node (ref "U2") (pin "53") (pinfunction "GND_53") (pintype "passive"))
      (node (ref "U2") (pin "63") (pinfunction "GND_63") (pintype "passive"))
      (node (ref "U2") (pin "73") (pinfunction "GND_73") (pintype "passive"))
      (node (ref "U2") (pin "84") (pinfunction "GND_84") (pintype "passive"))
      (node (ref "U3") (pin "10") (pinfunction "DVSS_10") (pintype "passive"))
      (node (ref "U3") (pin "12") (pinfunction "DVSS_12") (pintype "passive"))
      (node (ref "U3") (pin "16") (pinfunction "DVSS_16") (pintype "passive"))
      (node (ref "U3") (pin "18") (pinfunction "DVSS_18") (pintype "passive"))
      (node (ref "U3") (pin "21") (pinfunction "DVSS_21") (pintype "passive"))
      (node (ref "U3") (pin "9") (pinfunction "DVSS_9") (pintype "passive"))
      (node (ref "U5") (pin "1") (pinfunction "GND_1") (pintype "passive"))
      (node (ref "U5") (pin "2") (pinfunction "nEN_2") (pintype "passive"))
    )
    (net (code "36") (name "Net-(A1-OUT)") (class "Default")
      (node (ref "A1") (pin "1") (pinfunction "OUT_1") (pintype "passive"))
      (node (ref "CON1") (pin "2") (pinfunction "RF2_2") (pintype "passive"))
    )
    (net (code "37") (name "Net-(Bat1-Pad2)") (class "Default")
      (node (ref "Bat1") (pin "2") (pinfunction "2_2") (pintype "passive"))
      (node (ref "R26") (pin "1") (pinfunction "1_1") (pintype "passive"))
    )
    (net (code "38") (name "Net-(Bat1-Pad3)") (class "Default")
      (node (ref "Bat1") (pin "3") (pinfunction "3_3") (pintype "passive"))
      (node (ref "C25") (pin "1") (pinfunction "1_1") (pintype "passive"))
      (node (ref "IC1") (pin "5") (pinfunction "BAT_5") (pintype "bidirectional"))
      (node (ref "IC1") (pin "6") (pinfunction "BAT_6") (pintype "bidirectional"))
    )
    (net (code "39") (name "Net-(C15-Pad2)") (class "Default")
      (node (ref "C15") (pin "2") (pinfunction "2_2") (pintype "passive"))
      (node (ref "T1") (pin "4") (pinfunction "BAL_4") (pintype "passive"))
    )
    (net (code "40") (name "Net-(C16-Pad2)") (class "Default")
      (node (ref "C16") (pin "2") (pinfunction "2_2") (pintype "passive"))
      (node (ref "T1") (pin "3") (pinfunction "BAL_3") (pintype "passive"))
    )
    (net (code "41") (name "Net-(C17-Pad2)") (class "Default")
      (node (ref "C17") (pin "2") (pinfunction "2_2") (pintype "passive"))
      (node (ref "R9") (pin "2") (pinfunction "2_2") (pintype "passive"))
    )
    (net (code "42") (name "Net-(C28-Pad1)") (class "Default")
      (node (ref "C28") (pin "1") (pinfunction "1_1") (pintype "passive"))
      (node (ref "R22") (pin "1") (pinfunction "1_1") (pintype "passive"))
    )
    (net (code "43") (name "Net-(CB3-Pad2)") (class "Default")
      (node (ref "CB3") (pin "2") (pinfunction "2_2") (pintype "passive"))
      (node (ref "U3") (pin "13") (pinfunction "DVDD_13") (pintype "passive"))
      (node (ref "U3") (pin "14") (pinfunction "DVDD_14") (pintype "passive"))
    )
    (net (code "44") (name "Net-(CON1-RF1)") (class "Default")
      (node (ref "CON1") (pin "1") (pinfunction "RF1_1") (pintype "passive"))
      (node (ref "T1") (pin "1") (pinfunction "UNB_1") (pintype "passive"))
    )
    (net (code "45") (name "Net-(D1-A)") (class "Default")
      (node (ref "D1") (pin "1") (pinfunction "A_1") (pintype "passive"))
      (node (ref "R18") (pin "1") (pinfunction "1_1") (pintype "passive"))
    )
    (net (code "46") (name "Net-(D1-K)") (class "Default")
      (node (ref "D1") (pin "2") (pinfunction "K_2") (pintype "passive"))
      (node (ref "IC1") (pin "19") (pinfunction "/USBPG_19") (pintype "output"))
    )
    (net (code "47") (name "Net-(D2-A)") (class "Default")
      (node (ref "D2") (pin "1") (pinfunction "A_1") (pintype "passive"))
      (node (ref "R16") (pin "1") (pinfunction "1_1") (pintype "passive"))
    )
    (net (code "48") (name "Net-(D2-K)") (class "Default")
      (node (ref "D2") (pin "2") (pinfunction "K_2") (pintype "passive"))
      (node (ref "IC1") (pin "2") (pinfunction "STAT1_2") (pintype "output"))
    )
    (net (code "49") (name "Net-(D3-A)") (class "Default")
      (node (ref "D3") (pin "1") (pinfunction "A_1") (pintype "passive"))
      (node (ref "R17") (pin "1") (pinfunction "1_1") (pintype "passive"))
    )
    (net (code "50") (name "Net-(D3-K)") (class "Default")
      (node (ref "D3") (pin "2") (pinfunction "K_2") (pintype "passive"))
      (node (ref "IC1") (pin "3") (pinfunction "STAT2_3") (pintype "output"))
    )
    (net (code "51") (name "Net-(D4-A)") (class "Default")
      (node (ref "D4") (pin "1") (pinfunction "A_1") (pintype "passive"))
      (node (ref "R19") (pin "1") (pinfunction "1_1") (pintype "passive"))
    )
    (net (code "52") (name "Net-(D4-K)") (class "Default")
      (node (ref "D4") (pin "2") (pinfunction "K_2") (pintype "passive"))
      (node (ref "IC1") (pin "18") (pinfunction "/ACPG_18") (pintype "output"))
    )
    (net (code "53") (name "Net-(IC1-DPPM)") (class "Default")
      (node (ref "IC1") (pin "13") (pinfunction "DPPM_13") (pintype "input"))
      (node (ref "R23") (pin "1") (pinfunction "1_1") (pintype "passive"))
    )
    (net (code "54") (name "Net-(IC1-ISET1)") (class "Default")
      (node (ref "IC1") (pin "10") (pinfunction "ISET1_10") (pintype "bidirectional"))
      (node (ref "R29") (pin "2") (pinfunction "2_2") (pintype "passive"))
    )
    (net (code "55") (name "Net-(IC1-LDO)") (class "Default")
      (node (ref "C20") (pin "1") (pinfunction "1_1") (pintype "passive"))
      (node (ref "IC1") (pin "1") (pinfunction "LDO_1") (pintype "output"))
    )
    (net (code "56") (name "Net-(IC1-TMR)") (class "Default")
      (node (ref "IC1") (pin "14") (pinfunction "TMR_14") (pintype "bidirectional"))
      (node (ref "R24") (pin "1") (pinfunction "1_1") (pintype "passive"))
    )
    (net (code "57") (name "Net-(J1-S)") (class "Default")
      (node (ref "J1") (pin "1") (pinfunction "S_1") (pintype "passive"))
      (node (ref "R20") (pin "1") (pinfunction "1_1") (pintype "passive"))
    )
    (net (code "58") (name "Net-(T1-DC)") (class "Default")
      (node (ref "C12") (pin "2") (pinfunction "2_2") (pintype "passive"))
      (node (ref "T1") (pin "2") (pinfunction "DC_2") (pintype "passive"))
    )
    (net (code "59") (name "Net-(T2-TP)") (class "Default")
      (node (ref "R8") (pin "1") (pinfunction "1_1") (pintype "passive"))
      (node (ref "T2") (pin "1") (pinfunction "TP_1") (pintype "passive"))
      (node (ref "U3") (pin "7") (pinfunction "TST_7") (pintype "passive"))
    )
    (net (code "60") (name "Net-(U1-DCD)") (class "Default")
      (node (ref "R6") (pin "1") (pinfunction "1_1") (pintype "passive"))
      (node (ref "U1") (pin "1") (pinfunction "DCD_1") (pintype "passive"))
    )
    (net (code "61") (name "Net-(U1-RI)") (class "Default")
      (node (ref "R7") (pin "1") (pinfunction "1_1") (pintype "passive"))
      (node (ref "U1") (pin "2") (pinfunction "RI_2") (pintype "passive"))
    )
    (net (code "62") (name "Net-(U1-RXD)") (class "Default")
      (node (ref "R5") (pin "1") (pinfunction "1_1") (pintype "passive"))
      (node (ref "U1") (pin "25") (pinfunction "RXD_25") (pintype "passive"))
    )
    (net (code "63") (name "Net-(U1-SUSPEND)") (class "Default")
      (node (ref "R11") (pin "2") (pinfunction "2_2") (pintype "passive"))
      (node (ref "U1") (pin "12") (pinfunction "SUSPEND_12") (pintype "passive"))
    )
    (net (code "64") (name "Net-(U1-TXD)") (class "Default")
      (node (ref "R4") (pin "1") (pinfunction "1_1") (pintype "passive"))
      (node (ref "U1") (pin "26") (pinfunction "TXD_26") (pintype "passive"))
    )
    (net (code "65") (name "Net-(U1-nRST)") (class "Default")
      (node (ref "R12") (pin "2") (pinfunction "2_2") (pintype "passive"))
      (node (ref "U1") (pin "9") (pinfunction "nRST_9") (pintype "passive"))
    )
    (net (code "66") (name "Net-(U1-nSUSPEND)") (class "Default")
      (node (ref "R10") (pin "2") (pinfunction "2_2") (pintype "passive"))
      (node (ref "U1") (pin "11") (pinfunction "nSUSPEND_11") (pintype "passive"))
    )
    (net (code "67") (name "Net-(U2-PR0)") (class "Default")
      (node (ref "CX1") (pin "2") (pinfunction "2_2") (pintype "passive"))
      (node (ref "U2") (pin "91") (pinfunction "PR0_91") (pintype "passive"))
      (node (ref "Xtal1") (pin "3") (pinfunction "OSC2_3") (pintype "passive"))
    )
    (net (code "68") (name "Net-(U2-PR1)") (class "Default")
      (node (ref "CX2") (pin "2") (pinfunction "2_2") (pintype "passive"))
      (node (ref "U2") (pin "92") (pinfunction "PR1_92") (pintype "passive"))
      (node (ref "Xtal1") (pin "1") (pinfunction "OSC1_1") (pintype "passive"))
    )
    (net (code "69") (name "Net-(U3-AVDD)") (class "Default")
      (node (ref "CB1") (pin "2") (pinfunction "2_2") (pintype "passive"))
      (node (ref "U3") (pin "29") (pinfunction "AVDD_29") (pintype "passive"))
    )
    (net (code "70") (name "Net-(U3-CLKM)") (class "Default")
      (node (ref "R9") (pin "1") (pinfunction "1_1") (pintype "passive"))
      (node (ref "U3") (pin "17") (pinfunction "CLKM_17") (pintype "passive"))
    )
    (net (code "71") (name "Net-(U3-RFN)") (class "Default")
      (node (ref "C16") (pin "1") (pinfunction "1_1") (pintype "passive"))
      (node (ref "U3") (pin "5") (pinfunction "RFN_5") (pintype "passive"))
    )
    (net (code "72") (name "Net-(U3-RFP)") (class "Default")
      (node (ref "C15") (pin "1") (pinfunction "1_1") (pintype "passive"))
      (node (ref "U3") (pin "4") (pinfunction "RFP_4") (pintype "passive"))
    )
    (net (code "73") (name "Net-(U3-XTAL1)") (class "Default")
      (node (ref "CX4") (pin "2") (pinfunction "2_2") (pintype "passive"))
      (node (ref "U3") (pin "25") (pinfunction "XTAL1_25") (pintype "passive"))
      (node (ref "Xtal2") (pin "3") (pinfunction "OSC2_3") (pintype "passive"))
    )
    (net (code "74") (name "Net-(U3-XTAL2)") (class "Default")
      (node (ref "CX3") (pin "2") (pinfunction "2_2") (pintype "passive"))
      (node (ref "U3") (pin "26") (pinfunction "XTAL2_26") (pintype "passive"))
      (node (ref "Xtal2") (pin "1") (pinfunction "OSC1_1") (pintype "passive"))
    )
    (net (code "75") (name "Net-(U5-IN1)") (class "Default")
      (node (ref "C24") (pin "1") (pinfunction "1_1") (pintype "passive"))
      (node (ref "IC1") (pin "15") (pinfunction "OUT_15") (pintype "output"))
      (node (ref "IC1") (pin "16") (pinfunction "OUT_16") (pintype "output"))
      (node (ref "IC1") (pin "17") (pinfunction "OUT_17") (pintype "output"))
      (node (ref "U5") (pin "3") (pinfunction "IN1_3") (pintype "passive"))
      (node (ref "U5") (pin "4") (pinfunction "IN2_4") (pintype "passive"))
    )
    (net (code "76") (name "Net-(U5-PG)") (class "Default")
      (node (ref "R21") (pin "1") (pinfunction "1_1") (pintype "passive"))
      (node (ref "U5") (pin "8") (pinfunction "PG_8") (pintype "passive"))
    )
    (net (code "77") (name "RF-GND") (class "Default")
      (node (ref "C12") (pin "1") (pinfunction "1_1") (pintype "passive"))
      (node (ref "C29") (pin "1") (pinfunction "1_1") (pintype "passive"))
      (node (ref "CB1") (pin "1") (pinfunction "1_1") (pintype "passive"))
      (node (ref "CB2") (pin "1") (pinfunction "1_1") (pintype "passive"))
      (node (ref "CON1") (pin "3") (pinfunction "GND1_3") (pintype "passive"))
      (node (ref "CON1") (pin "4") (pinfunction "GND2_4") (pintype "passive"))
      (node (ref "CON1") (pin "5") (pinfunction "GND3_5") (pintype "passive"))
      (node (ref "CON1") (pin "6") (pinfunction "GND4_6") (pintype "passive"))
      (node (ref "CX3") (pin "1") (pinfunction "1_1") (pintype "passive"))
      (node (ref "CX4") (pin "1") (pinfunction "1_1") (pintype "passive"))
      (node (ref "L1") (pin "1") (pinfunction "1_1") (pintype "passive"))
      (node (ref "T1") (pin "5") (pinfunction "GND_5") (pintype "passive"))
      (node (ref "T1") (pin "6") (pinfunction "GND_6") (pintype "passive"))
      (node (ref "U3") (pin "1") (pinfunction "AVSS_1") (pintype "passive"))
      (node (ref "U3") (pin "2") (pinfunction "AVSS_2") (pintype "passive"))
      (node (ref "U3") (pin "27") (pinfunction "AVSS_27") (pintype "passive"))
      (node (ref "U3") (pin "3") (pinfunction "AVSS_3") (pintype "passive"))
      (node (ref "U3") (pin "30") (pinfunction "AVSS_30") (pintype "passive"))
      (node (ref "U3") (pin "31") (pinfunction "AVSS_31") (pintype "passive"))
      (node (ref "U3") (pin "32") (pinfunction "AVSS_32") (pintype "passive"))
      (node (ref "U3") (pin "33") (pinfunction "AVSS_33") (pintype "passive"))
      (node (ref "U3") (pin "6") (pinfunction "AVSS_6") (pintype "passive"))
    )
    (net (code "78") (name "RF-VCC") (class "Default")
      (node (ref "C26") (pin "2") (pinfunction "2_2") (pintype "passive"))
      (node (ref "CB2") (pin "2") (pinfunction "2_2") (pintype "passive"))
      (node (ref "L3") (pin "2") (pinfunction "2_2") (pintype "passive"))
      (node (ref "U3") (pin "28") (pinfunction "EVDD_28") (pintype "passive"))
    )
    (net (code "79") (name "U-GND") (class "Default")
      (node (ref "L6") (pin "1") (pinfunction "1_1") (pintype "passive"))
      (node (ref "P4") (pin "ID") (pinfunction "ID_ID") (pintype "passive"))
      (node (ref "P4") (pin "SHIELD") (pinfunction "SHIELD_SHIELD") (pintype "passive"))
      (node (ref "P4") (pin "UGND") (pinfunction "UGND_UGND") (pintype "passive"))
      (node (ref "U4") (pin "1") (pinfunction "GND_1") (pintype "passive"))
    )
    (net (code "80") (name "VCC") (class "Default")
      (node (ref "C1") (pin "1") (pinfunction "1_1") (pintype "passive"))
      (node (ref "C10") (pin "1") (pinfunction "1_1") (pintype "passive"))
      (node (ref "C11") (pin "1") (pinfunction "1_1") (pintype "passive"))
      (node (ref "C13") (pin "1") (pinfunction "1_1") (pintype "passive"))
      (node (ref "C18") (pin "1") (pinfunction "1_1") (pintype "passive"))
      (node (ref "C2") (pin "1") (pinfunction "1_1") (pintype "passive"))
      (node (ref "C23") (pin "1") (pinfunction "1_1") (pintype "passive"))
      (node (ref "C29") (pin "2") (pinfunction "2_2") (pintype "passive"))
      (node (ref "C3") (pin "1") (pinfunction "1_1") (pintype "passive"))
      (node (ref "C30") (pin "2") (pinfunction "2_2") (pintype "passive"))
      (node (ref "C4") (pin "1") (pinfunction "1_1") (pintype "passive"))
      (node (ref "C7") (pin "1") (pinfunction "1_1") (pintype "passive"))
      (node (ref "C8") (pin "1") (pinfunction "1_1") (pintype "passive"))
      (node (ref "C9") (pin "1") (pinfunction "1_1") (pintype "passive"))
      (node (ref "CB4") (pin "1") (pinfunction "1_1") (pintype "passive"))
      (node (ref "F1") (pin "1") (pinfunction "X_1") (pintype "passive"))
      (node (ref "L3") (pin "1") (pinfunction "1_1") (pintype "passive"))
      (node (ref "L4") (pin "1") (pinfunction "1_1") (pintype "passive"))
      (node (ref "P1") (pin "2") (pinfunction "2_2") (pintype "passive"))
      (node (ref "P2") (pin "4") (pinfunction "4_4") (pintype "passive"))
      (node (ref "R1") (pin "2") (pinfunction "2_2") (pintype "passive"))
      (node (ref "R12") (pin "1") (pinfunction "1_1") (pintype "passive"))
      (node (ref "R13") (pin "2") (pinfunction "2_2") (pintype "passive"))
      (node (ref "R14") (pin "2") (pinfunction "2_2") (pintype "passive"))
      (node (ref "R15") (pin "2") (pinfunction "2_2") (pintype "passive"))
      (node (ref "R16") (pin "2") (pinfunction "2_2") (pintype "passive"))
      (node (ref "R17") (pin "2") (pinfunction "2_2") (pintype "passive"))
      (node (ref "R18") (pin "2") (pinfunction "2_2") (pintype "passive"))
      (node (ref "R19") (pin "2") (pinfunction "2_2") (pintype "passive"))
      (node (ref "R21") (pin "2") (pinfunction "2_2") (pintype "passive"))
      (node (ref "R22") (pin "2") (pinfunction "2_2") (pintype "passive"))
      (node (ref "U1") (pin "6") (pinfunction "VDD_6") (pintype "passive"))
      (node (ref "U1") (pin "7") (pinfunction "REGIN_7") (pintype "passive"))
      (node (ref "U2") (pin "14") (pinfunction "VCC_14") (pintype "passive"))
      (node (ref "U2") (pin "24") (pinfunction "VCC_24") (pintype "passive"))
      (node (ref "U2") (pin "34") (pinfunction "VCC_34") (pintype "passive"))
      (node (ref "U2") (pin "44") (pinfunction "VCC_44") (pintype "passive"))
      (node (ref "U2") (pin "54") (pinfunction "VCC_54") (pintype "passive"))
      (node (ref "U2") (pin "64") (pinfunction "VCC_64") (pintype "passive"))
      (node (ref "U2") (pin "74") (pinfunction "VCC_74") (pintype "passive"))
      (node (ref "U2") (pin "83") (pinfunction "VCC_83") (pintype "passive"))
      (node (ref "U3") (pin "15") (pinfunction "DEVDD_15") (pintype "passive"))
      (node (ref "U5") (pin "5") (pinfunction "OUT1_5") (pintype "passive"))
      (node (ref "U5") (pin "6") (pinfunction "OUT2_6") (pintype "passive"))
    )
    (net (code "81") (name "unconnected-(P1-Pad3)") (class "Default")
      (node (ref "P1") (pin "3") (pinfunction "3_3") (pintype "passive"))
    )
    (net (code "82") (name "unconnected-(P1-Pad4)") (class "Default")
      (node (ref "P1") (pin "4") (pinfunction "4_4") (pintype "passive"))
    )
    (net (code "83") (name "unconnected-(P2-Pad7)") (class "Default")
      (node (ref "P2") (pin "7") (pinfunction "7_7") (pintype "passive"))
    )
    (net (code "84") (name "unconnected-(P2-Pad8)") (class "Default")
      (node (ref "P2") (pin "8") (pinfunction "8_8") (pintype "passive"))
    )
    (net (code "85") (name "unconnected-(U1-NC-Pad10)") (class "Default")
      (node (ref "U1") (pin "10") (pinfunction "NC_10") (pintype "passive"))
    )
    (net (code "86") (name "unconnected-(U1-NC-Pad13)") (class "Default")
      (node (ref "U1") (pin "13") (pinfunction "NC_13") (pintype "passive"))
    )
    (net (code "87") (name "unconnected-(U1-NC-Pad14)") (class "Default")
      (node (ref "U1") (pin "14") (pinfunction "NC_14") (pintype "passive"))
    )
    (net (code "88") (name "unconnected-(U1-NC-Pad15)") (class "Default")
      (node (ref "U1") (pin "15") (pinfunction "NC_15") (pintype "passive"))
    )
    (net (code "89") (name "unconnected-(U1-NC-Pad16)") (class "Default")
      (node (ref "U1") (pin "16") (pinfunction "NC_16") (pintype "passive"))
    )
    (net (code "90") (name "unconnected-(U1-NC-Pad17)") (class "Default")
      (node (ref "U1") (pin "17") (pinfunction "NC_17") (pintype "passive"))
    )
    (net (code "91") (name "unconnected-(U1-NC-Pad18)") (class "Default")
      (node (ref "U1") (pin "18") (pinfunction "NC_18") (pintype "passive"))
    )
    (net (code "92") (name "unconnected-(U1-NC-Pad19)") (class "Default")
      (node (ref "U1") (pin "19") (pinfunction "NC_19") (pintype "passive"))
    )
    (net (code "93") (name "unconnected-(U1-NC-Pad20)") (class "Default")
      (node (ref "U1") (pin "20") (pinfunction "NC_20") (pintype "passive"))
    )
    (net (code "94") (name "unconnected-(U1-NC-Pad21)") (class "Default")
      (node (ref "U1") (pin "21") (pinfunction "NC_21") (pintype "passive"))
    )
    (net (code "95") (name "unconnected-(U1-NC-Pad22)") (class "Default")
      (node (ref "U1") (pin "22") (pinfunction "NC_22") (pintype "passive"))
    )
    (net (code "96") (name "unconnected-(U2-PA0-Pad95)") (class "Default")
      (node (ref "U2") (pin "95") (pinfunction "PA0_95") (pintype "passive"))
    )
    (net (code "97") (name "unconnected-(U2-PA1-Pad96)") (class "Default")
      (node (ref "U2") (pin "96") (pinfunction "PA1_96") (pintype "passive"))
    )
    (net (code "98") (name "unconnected-(U2-PA2-Pad97)") (class "Default")
      (node (ref "U2") (pin "97") (pinfunction "PA2_97") (pintype "passive"))
    )
    (net (code "99") (name "unconnected-(U2-PA3-Pad98)") (class "Default")
      (node (ref "U2") (pin "98") (pinfunction "PA3_98") (pintype "passive"))
    )
    (net (code "100") (name "unconnected-(U2-PA4-Pad99)") (class "Default")
      (node (ref "U2") (pin "99") (pinfunction "PA4_99") (pintype "passive"))
    )
    (net (code "101") (name "unconnected-(U2-PA5-Pad100)") (class "Default")
      (node (ref "U2") (pin "100") (pinfunction "PA5_100") (pintype "passive"))
    )
    (net (code "102") (name "unconnected-(U2-PA6-Pad1)") (class "Default")
      (node (ref "U2") (pin "1") (pinfunction "PA6_1") (pintype "passive"))
    )
    (net (code "103") (name "unconnected-(U2-PA7-Pad2)") (class "Default")
      (node (ref "U2") (pin "2") (pinfunction "PA7_2") (pintype "passive"))
    )
    (net (code "104") (name "unconnected-(U2-PB0-Pad5)") (class "Default")
      (node (ref "U2") (pin "5") (pinfunction "PB0_5") (pintype "passive"))
    )
    (net (code "105") (name "unconnected-(U2-PB1-Pad6)") (class "Default")
      (node (ref "U2") (pin "6") (pinfunction "PB1_6") (pintype "passive"))
    )
    (net (code "106") (name "unconnected-(U2-PB2-Pad7)") (class "Default")
      (node (ref "U2") (pin "7") (pinfunction "PB2_7") (pintype "passive"))
    )
    (net (code "107") (name "unconnected-(U2-PB3-Pad8)") (class "Default")
      (node (ref "U2") (pin "8") (pinfunction "PB3_8") (pintype "passive"))
    )
    (net (code "108") (name "unconnected-(U2-PD0-Pad25)") (class "Default")
      (node (ref "U2") (pin "25") (pinfunction "PD0_25") (pintype "passive"))
    )
    (net (code "109") (name "unconnected-(U2-PD1-Pad26)") (class "Default")
      (node (ref "U2") (pin "26") (pinfunction "PD1_26") (pintype "passive"))
    )
    (net (code "110") (name "unconnected-(U2-PD2-Pad27)") (class "Default")
      (node (ref "U2") (pin "27") (pinfunction "PD2_27") (pintype "passive"))
    )
    (net (code "111") (name "unconnected-(U2-PD3-Pad28)") (class "Default")
      (node (ref "U2") (pin "28") (pinfunction "PD3_28") (pintype "passive"))
    )
    (net (code "112") (name "unconnected-(U2-PD4-Pad29)") (class "Default")
      (node (ref "U2") (pin "29") (pinfunction "PD4_29") (pintype "passive"))
    )
    (net (code "113") (name "unconnected-(U2-PD5-Pad30)") (class "Default")
      (node (ref "U2") (pin "30") (pinfunction "PD5_30") (pintype "passive"))
    )
    (net (code "114") (name "unconnected-(U2-PD6-Pad31)") (class "Default")
      (node (ref "U2") (pin "31") (pinfunction "PD6_31") (pintype "passive"))
    )
    (net (code "115") (name "unconnected-(U2-PD7-Pad32)") (class "Default")
      (node (ref "U2") (pin "32") (pinfunction "PD7_32") (pintype "passive"))
    )
    (net (code "116") (name "unconnected-(U2-PE0-Pad35)") (class "Default")
      (node (ref "U2") (pin "35") (pinfunction "PE0_35") (pintype "passive"))
    )
    (net (code "117") (name "unconnected-(U2-PE1-Pad36)") (class "Default")
      (node (ref "U2") (pin "36") (pinfunction "PE1_36") (pintype "passive"))
    )
    (net (code "118") (name "unconnected-(U2-PE2-Pad37)") (class "Default")
      (node (ref "U2") (pin "37") (pinfunction "PE2_37") (pintype "passive"))
    )
    (net (code "119") (name "unconnected-(U2-PE3-Pad38)") (class "Default")
      (node (ref "U2") (pin "38") (pinfunction "PE3_38") (pintype "passive"))
    )
    (net (code "120") (name "unconnected-(U2-PE4-Pad39)") (class "Default")
      (node (ref "U2") (pin "39") (pinfunction "PE4_39") (pintype "passive"))
    )
    (net (code "121") (name "unconnected-(U2-PE5-Pad40)") (class "Default")
      (node (ref "U2") (pin "40") (pinfunction "PE5_40") (pintype "passive"))
    )
    (net (code "122") (name "unconnected-(U2-PE6-Pad41)") (class "Default")
      (node (ref "U2") (pin "41") (pinfunction "PE6_41") (pintype "passive"))
    )
    (net (code "123") (name "unconnected-(U2-PE7-Pad42)") (class "Default")
      (node (ref "U2") (pin "42") (pinfunction "PE7_42") (pintype "passive"))
    )
    (net (code "124") (name "unconnected-(U2-PF0-Pad45)") (class "Default")
      (node (ref "U2") (pin "45") (pinfunction "PF0_45") (pintype "passive"))
    )
    (net (code "125") (name "unconnected-(U2-PH0-Pad55)") (class "Default")
      (node (ref "U2") (pin "55") (pinfunction "PH0_55") (pintype "passive"))
    )
    (net (code "126") (name "unconnected-(U2-PH1-Pad56)") (class "Default")
      (node (ref "U2") (pin "56") (pinfunction "PH1_56") (pintype "passive"))
    )
    (net (code "127") (name "unconnected-(U2-PH2-Pad57)") (class "Default")
      (node (ref "U2") (pin "57") (pinfunction "PH2_57") (pintype "passive"))
    )
    (net (code "128") (name "unconnected-(U2-PH3-Pad58)") (class "Default")
      (node (ref "U2") (pin "58") (pinfunction "PH3_58") (pintype "passive"))
    )
    (net (code "129") (name "unconnected-(U2-PH4-Pad59)") (class "Default")
      (node (ref "U2") (pin "59") (pinfunction "PH4_59") (pintype "passive"))
    )
    (net (code "130") (name "unconnected-(U2-PH5-Pad60)") (class "Default")
      (node (ref "U2") (pin "60") (pinfunction "PH5_60") (pintype "passive"))
    )
    (net (code "131") (name "unconnected-(U2-PH6-Pad61)") (class "Default")
      (node (ref "U2") (pin "61") (pinfunction "PH6_61") (pintype "passive"))
    )
    (net (code "132") (name "unconnected-(U2-PH7-Pad62)") (class "Default")
      (node (ref "U2") (pin "62") (pinfunction "PH7_62") (pintype "passive"))
    )
    (net (code "133") (name "unconnected-(U2-PJ0-Pad65)") (class "Default")
      (node (ref "U2") (pin "65") (pinfunction "PJ0_65") (pintype "passive"))
    )
    (net (code "134") (name "unconnected-(U2-PJ1-Pad66)") (class "Default")
      (node (ref "U2") (pin "66") (pinfunction "PJ1_66") (pintype "passive"))
    )
    (net (code "135") (name "unconnected-(U2-PJ2-Pad67)") (class "Default")
      (node (ref "U2") (pin "67") (pinfunction "PJ2_67") (pintype "passive"))
    )
    (net (code "136") (name "unconnected-(U2-PJ3-Pad68)") (class "Default")
      (node (ref "U2") (pin "68") (pinfunction "PJ3_68") (pintype "passive"))
    )
    (net (code "137") (name "unconnected-(U2-PJ4-Pad69)") (class "Default")
      (node (ref "U2") (pin "69") (pinfunction "PJ4_69") (pintype "passive"))
    )
    (net (code "138") (name "unconnected-(U2-PJ5-Pad70)") (class "Default")
      (node (ref "U2") (pin "70") (pinfunction "PJ5_70") (pintype "passive"))
    )
    (net (code "139") (name "unconnected-(U2-PJ6-Pad71)") (class "Default")
      (node (ref "U2") (pin "71") (pinfunction "PJ6_71") (pintype "passive"))
    )
    (net (code "140") (name "unconnected-(U2-PJ7-Pad72)") (class "Default")
      (node (ref "U2") (pin "72") (pinfunction "PJ7_72") (pintype "passive"))
    )
    (net (code "141") (name "unconnected-(U2-PK0-Pad75)") (class "Default")
      (node (ref "U2") (pin "75") (pinfunction "PK0_75") (pintype "passive"))
    )
    (net (code "142") (name "unconnected-(U2-PK1-Pad76)") (class "Default")
      (node (ref "U2") (pin "76") (pinfunction "PK1_76") (pintype "passive"))
    )
    (net (code "143") (name "unconnected-(U2-PK2-Pad77)") (class "Default")
      (node (ref "U2") (pin "77") (pinfunction "PK2_77") (pintype "passive"))
    )
    (net (code "144") (name "unconnected-(U2-PK3-Pad78)") (class "Default")
      (node (ref "U2") (pin "78") (pinfunction "PK3_78") (pintype "passive"))
    )
    (net (code "145") (name "unconnected-(U2-PK4-Pad79)") (class "Default")
      (node (ref "U2") (pin "79") (pinfunction "PK4_79") (pintype "passive"))
    )
    (net (code "146") (name "unconnected-(U2-PK5-Pad80)") (class "Default")
      (node (ref "U2") (pin "80") (pinfunction "PK5_80") (pintype "passive"))
    )
    (net (code "147") (name "unconnected-(U2-PK6-Pad81)") (class "Default")
      (node (ref "U2") (pin "81") (pinfunction "PK6_81") (pintype "passive"))
    )
    (net (code "148") (name "unconnected-(U2-PK7-Pad82)") (class "Default")
      (node (ref "U2") (pin "82") (pinfunction "PK7_82") (pintype "passive"))
    )
    (net (code "149") (name "unconnected-(U2-PQ0-Pad85)") (class "Default")
      (node (ref "U2") (pin "85") (pinfunction "PQ0_85") (pintype "passive"))
    )
    (net (code "150") (name "unconnected-(U2-PQ1-Pad86)") (class "Default")
      (node (ref "U2") (pin "86") (pinfunction "PQ1_86") (pintype "passive"))
    )
    (net (code "151") (name "unconnected-(U2-PQ2-Pad87)") (class "Default")
      (node (ref "U2") (pin "87") (pinfunction "PQ2_87") (pintype "passive"))
    )
    (net (code "152") (name "unconnected-(U2-PQ3-Pad88)") (class "Default")
      (node (ref "U2") (pin "88") (pinfunction "PQ3_88") (pintype "passive"))
    )
    (net (code "153") (name "unconnected-(U5-FB-Pad7)") (class "Default")
      (node (ref "U5") (pin "7") (pinfunction "FB_7") (pintype "passive"))
    )
    (net (code "154") (name "unconnected-(Xtal1-OSC2-Pad2)") (class "Default")
      (node (ref "Xtal1") (pin "2") (pinfunction "OSC2_2") (pintype "passive"))
    )
    (net (code "155") (name "unconnected-(Xtal1-OSC2-Pad4)") (class "Default")
      (node (ref "Xtal1") (pin "4") (pinfunction "OSC2_4") (pintype "passive"))
    )
    (net (code "156") (name "unconnected-(Xtal2-OSC2-Pad2)") (class "Default")
      (node (ref "Xtal2") (pin "2") (pinfunction "OSC2_2") (pintype "passive"))
    )
    (net (code "157") (name "unconnected-(Xtal2-OSC2-Pad4)") (class "Default")
      (node (ref "Xtal2") (pin "4") (pinfunction "OSC2_4") (pintype "passive"))
    )
  )
)
